# RailroadShield.net
KiCad netlist of a schematic drawn in EAGLE
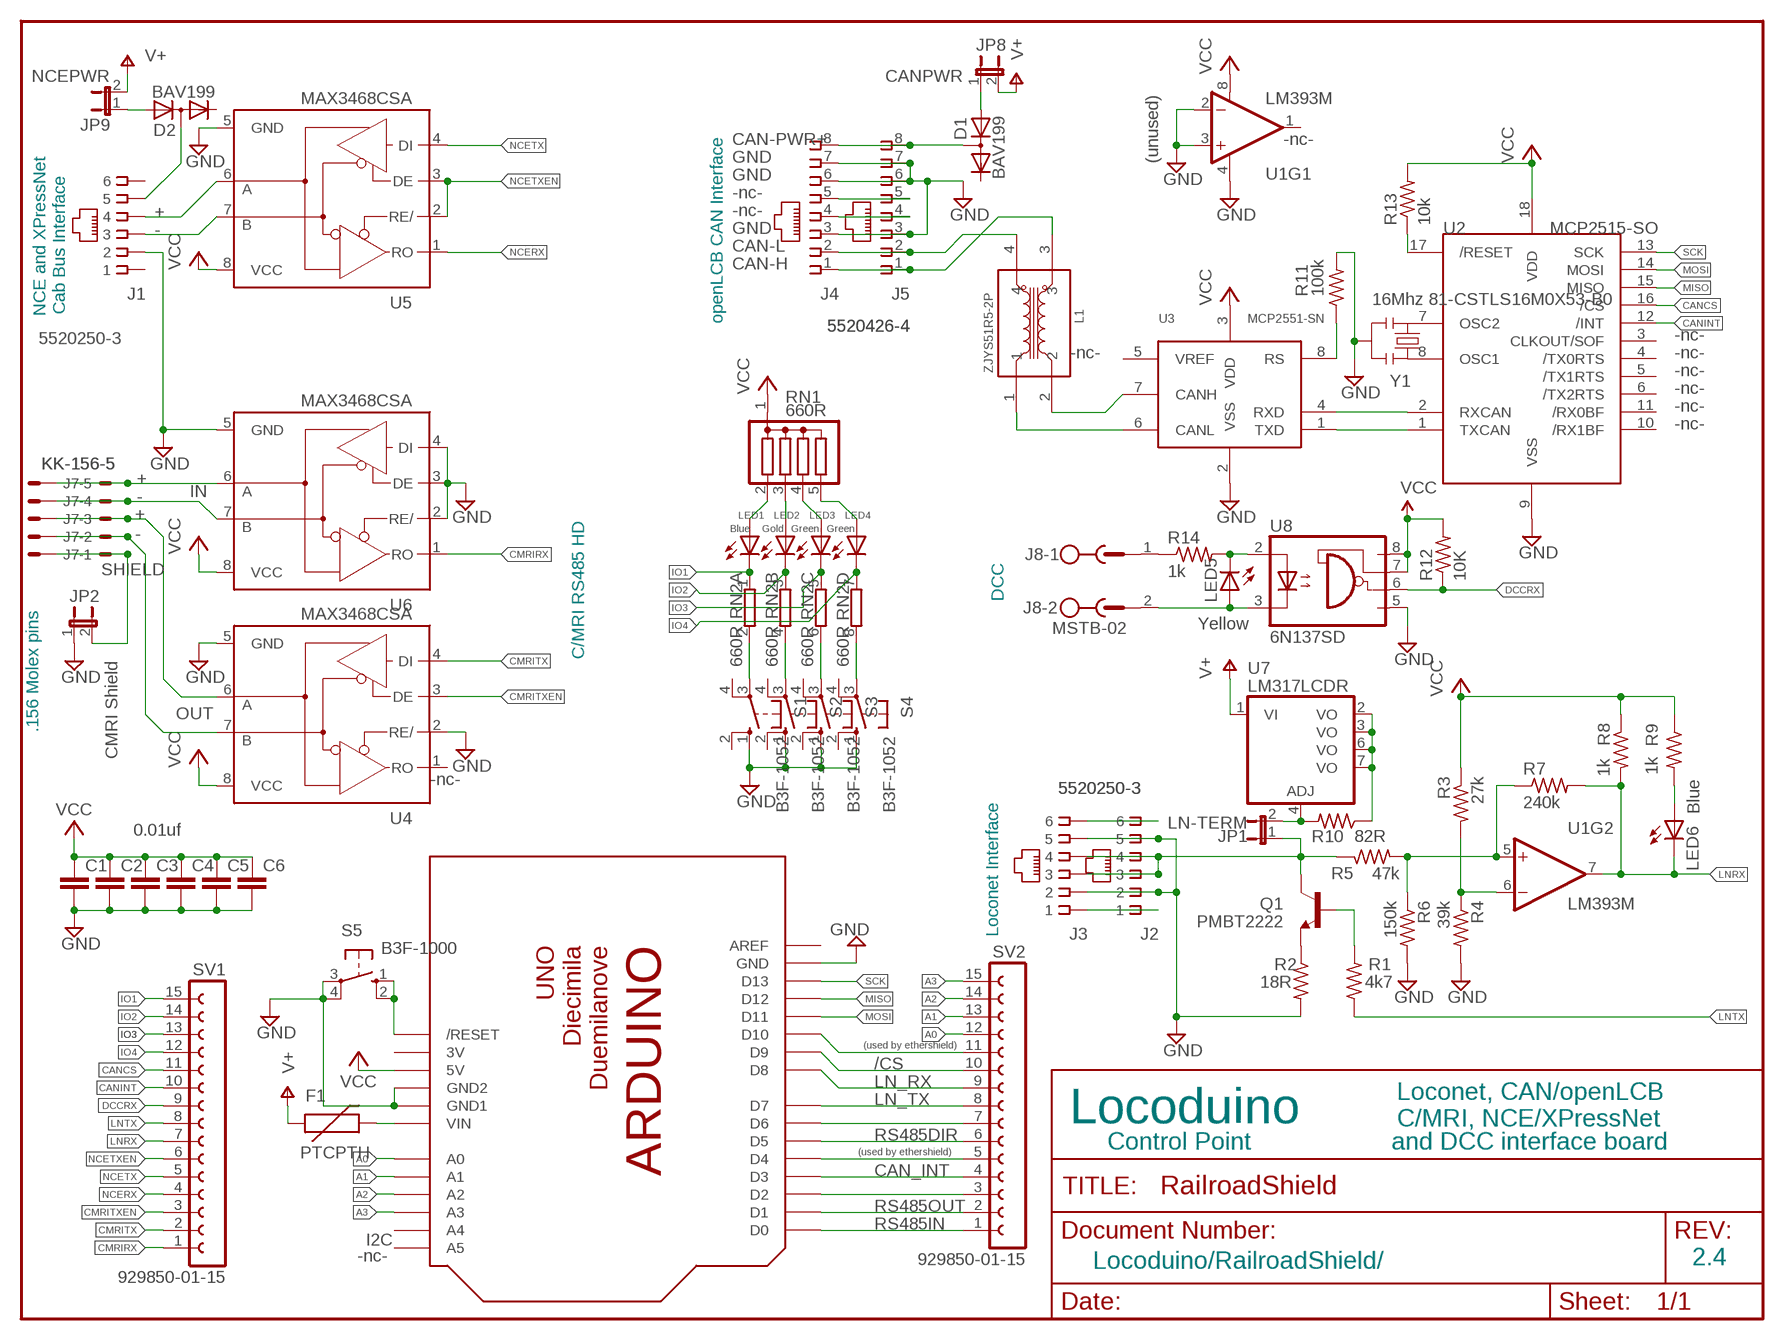
[diagram p0: schematic, sheet 1]

(export (version "E")
  (design (tool "Eeschema 10.0.6"))
  (components
    (comp (ref "C1")
      (value "0.01uf")
      (footprint "eagle-import:0805")
      (libsource (lib "eagle-import") (part "CAP0805"))
    )
    (comp (ref "C2")
      (value "0.01uf")
      (footprint "eagle-import:0805")
      (libsource (lib "eagle-import") (part "CAP0805"))
    )
    (comp (ref "C3")
      (value "0.01uf")
      (footprint "eagle-import:0805")
      (libsource (lib "eagle-import") (part "CAP0805"))
    )
    (comp (ref "C4")
      (value "0.01uf")
      (footprint "eagle-import:0805")
      (libsource (lib "eagle-import") (part "CAP0805"))
    )
    (comp (ref "C5")
      (value "0.01uf")
      (footprint "eagle-import:0805")
      (libsource (lib "eagle-import") (part "CAP0805"))
    )
    (comp (ref "C6")
      (value "0.01uf")
      (footprint "eagle-import:0805")
      (libsource (lib "eagle-import") (part "CAP0805"))
    )
    (comp (ref "D1")
      (value "BAV199")
      (footprint "eagle-import:SOT23")
      (libsource (lib "eagle-import") (part "BAV199"))
    )
    (comp (ref "D2")
      (value "BAV199")
      (footprint "eagle-import:SOT23")
      (libsource (lib "eagle-import") (part "BAV199"))
    )
    (comp (ref "F1")
      (value "PTCPTH")
      (footprint "eagle-import:PTC")
      (libsource (lib "eagle-import") (part "PTCPTH"))
    )
    (comp (ref "J1")
      (value "5520250-3")
      (footprint "eagle-import:RJ11-NO_SHIELD")
      (libsource (lib "eagle-import") (part "RJ11RA-6X"))
    )
    (comp (ref "J2")
      (value "5520250-3")
      (footprint "eagle-import:RJ11-NO_SHIELD")
      (libsource (lib "eagle-import") (part "RJ11RA-6X"))
    )
    (comp (ref "J3")
      (value "5520250-3")
      (footprint "eagle-import:RJ11-NO_SHIELD")
      (libsource (lib "eagle-import") (part "RJ11RA-6X"))
    )
    (comp (ref "J4")
      (value "5520426-4")
      (footprint "eagle-import:RJ45-NO-SHIELD")
      (libsource (lib "eagle-import") (part "RJ45-8X"))
    )
    (comp (ref "J5")
      (value "5520426-4")
      (footprint "eagle-import:RJ45-NO-SHIELD")
      (libsource (lib "eagle-import") (part "RJ45-8X"))
    )
    (comp (ref "J6")
      (value "KK-156-5")
      (footprint "eagle-import:KK-156-5")
      (libsource (lib "eagle-import") (part "KK-156-5"))
    )
    (comp (ref "J7")
      (value "KK-156-5")
      (footprint "eagle-import:KK-156-5")
      (libsource (lib "eagle-import") (part "KK-156-5"))
    )
    (comp (ref "J8")
      (value "MSTB-02")
      (footprint "eagle-import:MSTBV2")
      (libsource (lib "eagle-import") (part "MSTBV2"))
    )
    (comp (ref "JP1")
      (value "LN-TERM")
      (footprint "eagle-import:1X02_LOCK")
      (libsource (lib "eagle-import") (part "JUMPER-2PTH_LOCK"))
    )
    (comp (ref "JP2")
      (value "CMRI Shield")
      (footprint "eagle-import:1X02_LOCK")
      (libsource (lib "eagle-import") (part "JUMPER-2PTH_LOCK"))
    )
    (comp (ref "JP8")
      (value "CANPWR")
      (footprint "eagle-import:1X02_LOCK")
      (libsource (lib "eagle-import") (part "JUMPER-2PTH_LOCK"))
    )
    (comp (ref "JP9")
      (value "NCEPWR")
      (footprint "eagle-import:1X02_LOCK")
      (libsource (lib "eagle-import") (part "JUMPER-2PTH_LOCK"))
    )
    (comp (ref "L1")
      (value "ZJYS51R5-2P")
      (footprint "eagle-import:ZJYS")
      (libsource (lib "eagle-import") (part "ZJYS51R5-2P"))
    )
    (comp (ref "LED1")
      (value "Blue")
      (footprint "eagle-import:CHIP-LED0805")
      (libsource (lib "eagle-import") (part "LEDCHIP-LED0805"))
    )
    (comp (ref "LED2")
      (value "Gold")
      (footprint "eagle-import:CHIP-LED0805")
      (libsource (lib "eagle-import") (part "LEDCHIP-LED0805"))
    )
    (comp (ref "LED3")
      (value "Green")
      (footprint "eagle-import:CHIP-LED0805")
      (libsource (lib "eagle-import") (part "LEDCHIP-LED0805"))
    )
    (comp (ref "LED4")
      (value "Green")
      (footprint "eagle-import:CHIP-LED0805")
      (libsource (lib "eagle-import") (part "LEDCHIP-LED0805"))
    )
    (comp (ref "LED5")
      (value "Yellow")
      (footprint "eagle-import:CHIP-LED0805")
      (libsource (lib "eagle-import") (part "LEDCHIP-LED0805"))
    )
    (comp (ref "LED6")
      (value "Blue")
      (footprint "eagle-import:CHIP-LED0805")
      (libsource (lib "eagle-import") (part "LEDCHIP-LED0805"))
    )
    (comp (ref "Q1")
      (value "PMBT2222")
      (footprint "eagle-import:SOT23-3")
      (libsource (lib "eagle-import") (part "TRANSISTOR_NPNSOT23-3"))
    )
    (comp (ref "R1")
      (value "4k7")
      (footprint "eagle-import:R0805")
      (libsource (lib "eagle-import") (part "R-US_R0805"))
    )
    (comp (ref "R2")
      (value "18R")
      (footprint "eagle-import:R0805")
      (libsource (lib "eagle-import") (part "R-US_R0805"))
    )
    (comp (ref "R3")
      (value "27k")
      (footprint "eagle-import:R0805")
      (libsource (lib "eagle-import") (part "R-US_R0805"))
    )
    (comp (ref "R4")
      (value "39k")
      (footprint "eagle-import:R0805")
      (libsource (lib "eagle-import") (part "R-US_R0805"))
    )
    (comp (ref "R5")
      (value "47k")
      (footprint "eagle-import:R0805")
      (libsource (lib "eagle-import") (part "R-US_R0805"))
    )
    (comp (ref "R6")
      (value "150k")
      (footprint "eagle-import:R0805")
      (libsource (lib "eagle-import") (part "R-US_R0805"))
    )
    (comp (ref "R7")
      (value "240k")
      (footprint "eagle-import:R0805")
      (libsource (lib "eagle-import") (part "R-US_R0805"))
    )
    (comp (ref "R8")
      (value "1k")
      (footprint "eagle-import:R0805")
      (libsource (lib "eagle-import") (part "R-US_R0805"))
    )
    (comp (ref "R9")
      (value "1k")
      (footprint "eagle-import:R0805")
      (libsource (lib "eagle-import") (part "R-US_R0805"))
    )
    (comp (ref "R10")
      (value "82R")
      (footprint "eagle-import:R0805")
      (libsource (lib "eagle-import") (part "R-US_R0805"))
    )
    (comp (ref "R11")
      (value "100k")
      (footprint "eagle-import:R0805")
      (libsource (lib "eagle-import") (part "R-US_R0805"))
    )
    (comp (ref "R12")
      (value "10K")
      (footprint "eagle-import:R0805")
      (libsource (lib "eagle-import") (part "R-US_R0805"))
    )
    (comp (ref "R13")
      (value "10k")
      (footprint "eagle-import:R0805")
      (libsource (lib "eagle-import") (part "R-US_R0805"))
    )
    (comp (ref "R14")
      (value "1k")
      (footprint "eagle-import:R0805")
      (libsource (lib "eagle-import") (part "R-US_R0805"))
    )
    (comp (ref "RN1")
      (value "660R")
      (footprint "eagle-import:SIL5")
      (libsource (lib "eagle-import") (part "G04R"))
    )
    (comp (ref "RN2")
      (value "660R")
      (footprint "eagle-import:SIL8")
      (libsource (lib "eagle-import") (part "E4R"))
    )
    (comp (ref "S1")
      (value "B3F-1052")
      (footprint "eagle-import:B3F-10XX")
      (libsource (lib "eagle-import") (part "10-XX"))
    )
    (comp (ref "S2")
      (value "B3F-1052")
      (footprint "eagle-import:B3F-10XX")
      (libsource (lib "eagle-import") (part "10-XX"))
    )
    (comp (ref "S3")
      (value "B3F-1052")
      (footprint "eagle-import:B3F-10XX")
      (libsource (lib "eagle-import") (part "10-XX"))
    )
    (comp (ref "S4")
      (value "B3F-1052")
      (footprint "eagle-import:B3F-10XX")
      (libsource (lib "eagle-import") (part "10-XX"))
    )
    (comp (ref "S5")
      (value "B3F-1000")
      (footprint "eagle-import:B3F-10XX")
      (libsource (lib "eagle-import") (part "10-XX"))
    )
    (comp (ref "SV1")
      (value "929850-01-15")
      (footprint "eagle-import:FE15")
      (libsource (lib "eagle-import") (part "FE15-1"))
    )
    (comp (ref "SV2")
      (value "929850-01-15")
      (footprint "eagle-import:FE15")
      (libsource (lib "eagle-import") (part "FE15-1"))
    )
    (comp (ref "U$1")
      (value "ARDUINODUEMILANOVE")
      (footprint "eagle-import:ARDUINO-BIGSHIELD")
      (libsource (lib "eagle-import") (part "ARDUINODUEMILANOVE"))
    )
    (comp (ref "U1")
      (value "LM393M")
      (footprint "eagle-import:SO08")
      (libsource (lib "eagle-import") (part "LM393M"))
    )
    (comp (ref "U2")
      (value "MCP2515-SO")
      (footprint "eagle-import:SO-18W")
      (libsource (lib "eagle-import") (part "MCP2515-SO"))
    )
    (comp (ref "U3")
      (value "MCP2551-SN")
      (footprint "eagle-import:SO-08")
      (libsource (lib "eagle-import") (part "MCP2551-SN"))
    )
    (comp (ref "U4")
      (value "MAX3468CSA")
      (footprint "eagle-import:SO08")
      (libsource (lib "eagle-import") (part "MAX34SA68C"))
    )
    (comp (ref "U5")
      (value "MAX3468CSA")
      (footprint "eagle-import:SO08")
      (libsource (lib "eagle-import") (part "MAX34SA68C"))
    )
    (comp (ref "U6")
      (value "MAX3468CSA")
      (footprint "eagle-import:SO08")
      (libsource (lib "eagle-import") (part "MAX34SA68C"))
    )
    (comp (ref "U7")
      (value "LM317LCDR")
      (footprint "eagle-import:SO08")
      (libsource (lib "eagle-import") (part "LM317LD"))
    )
    (comp (ref "U8")
      (value "6N137SD")
      (footprint "eagle-import:SM8")
      (libsource (lib "eagle-import") (part "6N137S"))
    )
    (comp (ref "Y1")
      (value "16Mhz 81-CSTLS16M0X53-B0")
      (footprint "eagle-import:RESONATOR-PTH")
      (libsource (lib "eagle-import") (part "RESONATORPTH"))
    )
  )
  (nets
    (net (code "1") (name "/3V") (class "Default")
      (node (ref "U$1") (pin "3V") (pinfunction "3V_3V") (pintype "power_in"))
    )
    (net (code "2") (name "/CAN-H") (class "Default")
      (node (ref "J4") (pin "1") (pinfunction "1_1") (pintype "passive"))
      (node (ref "J5") (pin "1") (pinfunction "1_1") (pintype "passive"))
      (node (ref "L1") (pin "3") (pinfunction "3_3") (pintype "bidirectional"))
    )
    (net (code "3") (name "/CAN-L") (class "Default")
      (node (ref "J4") (pin "2") (pinfunction "2_2") (pintype "passive"))
      (node (ref "J5") (pin "2") (pinfunction "2_2") (pintype "passive"))
      (node (ref "L1") (pin "4") (pinfunction "4_4") (pintype "bidirectional"))
    )
    (net (code "4") (name "/CAN-PWR+") (class "Default")
      (node (ref "D1") (pin "3") (pinfunction "AC_3") (pintype "passive"))
      (node (ref "J4") (pin "8") (pinfunction "8_8") (pintype "passive"))
      (node (ref "J5") (pin "8") (pinfunction "8_8") (pintype "passive"))
    )
    (net (code "5") (name "A0") (class "Default")
      (node (ref "SV2") (pin "12") (pinfunction "12_12") (pintype "passive"))
      (node (ref "U$1") (pin "A0") (pinfunction "A0_A0") (pintype "bidirectional"))
    )
    (net (code "6") (name "A1") (class "Default")
      (node (ref "SV2") (pin "13") (pinfunction "13_13") (pintype "passive"))
      (node (ref "U$1") (pin "A1") (pinfunction "A1_A1") (pintype "bidirectional"))
    )
    (net (code "7") (name "A2") (class "Default")
      (node (ref "SV2") (pin "14") (pinfunction "14_14") (pintype "passive"))
      (node (ref "U$1") (pin "A2") (pinfunction "A2_A2") (pintype "bidirectional"))
    )
    (net (code "8") (name "A3") (class "Default")
      (node (ref "SV2") (pin "15") (pinfunction "15_15") (pintype "passive"))
      (node (ref "U$1") (pin "A3") (pinfunction "A3_A3") (pintype "bidirectional"))
    )
    (net (code "9") (name "CANCS") (class "Default")
      (node (ref "SV1") (pin "11") (pinfunction "11_11") (pintype "passive"))
      (node (ref "U2") (pin "16") (pinfunction "/CS_16") (pintype "bidirectional"))
    )
    (net (code "10") (name "CANINT") (class "Default")
      (node (ref "SV1") (pin "10") (pinfunction "10_10") (pintype "passive"))
      (node (ref "U2") (pin "12") (pinfunction "/INT_12") (pintype "output"))
    )
    (net (code "11") (name "CMRIRX") (class "Default")
      (node (ref "SV1") (pin "1") (pinfunction "1_1") (pintype "passive"))
      (node (ref "U6") (pin "1") (pinfunction "RO_1") (pintype "output"))
    )
    (net (code "12") (name "CMRITX") (class "Default")
      (node (ref "SV1") (pin "2") (pinfunction "2_2") (pintype "passive"))
      (node (ref "U4") (pin "4") (pinfunction "DI_4") (pintype "input"))
    )
    (net (code "13") (name "CMRITXEN") (class "Default")
      (node (ref "SV1") (pin "3") (pinfunction "3_3") (pintype "passive"))
      (node (ref "U4") (pin "3") (pinfunction "DE_3") (pintype "input"))
    )
    (net (code "14") (name "DCCRX") (class "Default")
      (node (ref "R12") (pin "1") (pinfunction "1_1") (pintype "passive"))
      (node (ref "SV1") (pin "9") (pinfunction "9_9") (pintype "passive"))
      (node (ref "U8") (pin "6") (pinfunction "VO_6") (pintype "passive"))
    )
    (net (code "15") (name "GND") (class "Default")
      (node (ref "C1") (pin "2") (pinfunction "2_2") (pintype "passive"))
      (node (ref "C2") (pin "2") (pinfunction "2_2") (pintype "passive"))
      (node (ref "C3") (pin "2") (pinfunction "2_2") (pintype "passive"))
      (node (ref "C4") (pin "2") (pinfunction "2_2") (pintype "passive"))
      (node (ref "C5") (pin "2") (pinfunction "2_2") (pintype "passive"))
      (node (ref "C6") (pin "2") (pinfunction "2_2") (pintype "passive"))
      (node (ref "J1") (pin "2") (pinfunction "2_2") (pintype "passive"))
      (node (ref "J2") (pin "2") (pinfunction "2_2") (pintype "passive"))
      (node (ref "J2") (pin "5") (pinfunction "5_5") (pintype "passive"))
      (node (ref "J3") (pin "2") (pinfunction "2_2") (pintype "passive"))
      (node (ref "J3") (pin "5") (pinfunction "5_5") (pintype "passive"))
      (node (ref "J4") (pin "3") (pinfunction "3_3") (pintype "passive"))
      (node (ref "J4") (pin "6") (pinfunction "6_6") (pintype "passive"))
      (node (ref "J4") (pin "7") (pinfunction "7_7") (pintype "passive"))
      (node (ref "J5") (pin "3") (pinfunction "3_3") (pintype "passive"))
      (node (ref "J5") (pin "6") (pinfunction "6_6") (pintype "passive"))
      (node (ref "J5") (pin "7") (pinfunction "7_7") (pintype "passive"))
      (node (ref "JP2") (pin "1") (pinfunction "1_1") (pintype "passive"))
      (node (ref "R11") (pin "2") (pinfunction "2_2") (pintype "passive"))
      (node (ref "R2") (pin "2") (pinfunction "2_2") (pintype "passive"))
      (node (ref "R4") (pin "2") (pinfunction "2_2") (pintype "passive"))
      (node (ref "R6") (pin "2") (pinfunction "2_2") (pintype "passive"))
      (node (ref "S1") (pin "1") (pinfunction "S_1") (pintype "passive"))
      (node (ref "S2") (pin "1") (pinfunction "S_1") (pintype "passive"))
      (node (ref "S3") (pin "1") (pinfunction "S_1") (pintype "passive"))
      (node (ref "S4") (pin "1") (pinfunction "S_1") (pintype "passive"))
      (node (ref "S5") (pin "3") (pinfunction "P_3") (pintype "passive"))
      (node (ref "S5") (pin "4") (pinfunction "P1_4") (pintype "passive"))
      (node (ref "U$1") (pin "GND") (pinfunction "GND_GND") (pintype "power_in"))
      (node (ref "U$1") (pin "GND1") (pinfunction "GND1_GND1") (pintype "power_in"))
      (node (ref "U$1") (pin "GND2") (pinfunction "GND2_GND2") (pintype "power_in"))
      (node (ref "U1") (pin "2") (pinfunction "-IN_2") (pintype "input"))
      (node (ref "U1") (pin "3") (pinfunction "+IN_3") (pintype "input"))
      (node (ref "U1") (pin "4") (pinfunction "V-_4") (pintype "power_in"))
      (node (ref "U2") (pin "9") (pinfunction "VSS_9") (pintype "power_in"))
      (node (ref "U3") (pin "2") (pinfunction "VSS_2") (pintype "power_in"))
      (node (ref "U4") (pin "2") (pinfunction "RE/_2") (pintype "input"))
      (node (ref "U4") (pin "5") (pinfunction "GND_5") (pintype "power_in"))
      (node (ref "U5") (pin "5") (pinfunction "GND_5") (pintype "power_in"))
      (node (ref "U6") (pin "2") (pinfunction "RE/_2") (pintype "input"))
      (node (ref "U6") (pin "3") (pinfunction "DE_3") (pintype "input"))
      (node (ref "U6") (pin "4") (pinfunction "DI_4") (pintype "input"))
      (node (ref "U6") (pin "5") (pinfunction "GND_5") (pintype "power_in"))
      (node (ref "U8") (pin "5") (pinfunction "GND_5") (pintype "passive"))
      (node (ref "Y1") (pin "2") (pinfunction "2_2") (pintype "passive"))
    )
    (net (code "16") (name "IO1") (class "Default")
      (node (ref "LED1") (pin "C") (pinfunction "C_C") (pintype "passive"))
      (node (ref "RN2") (pin "1") (pinfunction "1_1") (pintype "passive"))
      (node (ref "SV1") (pin "15") (pinfunction "15_15") (pintype "passive"))
    )
    (net (code "17") (name "IO2") (class "Default")
      (node (ref "LED2") (pin "C") (pinfunction "C_C") (pintype "passive"))
      (node (ref "RN2") (pin "3") (pinfunction "1_3") (pintype "passive"))
      (node (ref "SV1") (pin "14") (pinfunction "14_14") (pintype "passive"))
    )
    (net (code "18") (name "IO3") (class "Default")
      (node (ref "LED3") (pin "C") (pinfunction "C_C") (pintype "passive"))
      (node (ref "RN2") (pin "5") (pinfunction "1_5") (pintype "passive"))
      (node (ref "SV1") (pin "13") (pinfunction "13_13") (pintype "passive"))
    )
    (net (code "19") (name "IO4") (class "Default")
      (node (ref "LED4") (pin "C") (pinfunction "C_C") (pintype "passive"))
      (node (ref "RN2") (pin "7") (pinfunction "1_7") (pintype "passive"))
      (node (ref "SV1") (pin "12") (pinfunction "12_12") (pintype "passive"))
    )
    (net (code "20") (name "LNRX") (class "Default")
      (node (ref "LED6") (pin "C") (pinfunction "C_C") (pintype "passive"))
      (node (ref "R7") (pin "2") (pinfunction "2_2") (pintype "passive"))
      (node (ref "R8") (pin "2") (pinfunction "2_2") (pintype "passive"))
      (node (ref "SV1") (pin "7") (pinfunction "7_7") (pintype "passive"))
      (node (ref "U1") (pin "7") (pinfunction "OUT_7") (pintype "output"))
    )
    (net (code "21") (name "LNTX") (class "Default")
      (node (ref "R1") (pin "1") (pinfunction "1_1") (pintype "passive"))
      (node (ref "SV1") (pin "8") (pinfunction "8_8") (pintype "passive"))
    )
    (net (code "22") (name "MISO") (class "Default")
      (node (ref "U$1") (pin "D12") (pinfunction "D12_D12") (pintype "bidirectional"))
      (node (ref "U2") (pin "15") (pinfunction "MISO_15") (pintype "bidirectional"))
    )
    (net (code "23") (name "MOSI") (class "Default")
      (node (ref "U$1") (pin "D11") (pinfunction "D11_D11") (pintype "bidirectional"))
      (node (ref "U2") (pin "14") (pinfunction "MOSI_14") (pintype "bidirectional"))
    )
    (net (code "24") (name "NCERX") (class "Default")
      (node (ref "SV1") (pin "4") (pinfunction "4_4") (pintype "passive"))
      (node (ref "U5") (pin "1") (pinfunction "RO_1") (pintype "output"))
    )
    (net (code "25") (name "NCETX") (class "Default")
      (node (ref "SV1") (pin "5") (pinfunction "5_5") (pintype "passive"))
      (node (ref "U5") (pin "4") (pinfunction "DI_4") (pintype "input"))
    )
    (net (code "26") (name "NCETXEN") (class "Default")
      (node (ref "SV1") (pin "6") (pinfunction "6_6") (pintype "passive"))
      (node (ref "U5") (pin "2") (pinfunction "RE/_2") (pintype "input"))
      (node (ref "U5") (pin "3") (pinfunction "DE_3") (pintype "input"))
    )
    (net (code "27") (name "Net-(D1-A)") (class "Default")
      (node (ref "D1") (pin "1") (pinfunction "A_1") (pintype "passive"))
      (node (ref "JP8") (pin "1") (pinfunction "1_1") (pintype "passive"))
    )
    (net (code "28") (name "Net-(D2-A)") (class "Default")
      (node (ref "D2") (pin "1") (pinfunction "A_1") (pintype "passive"))
      (node (ref "JP9") (pin "1") (pinfunction "1_1") (pintype "passive"))
    )
    (net (code "29") (name "Net-(D2-AC)") (class "Default")
      (node (ref "D2") (pin "3") (pinfunction "AC_3") (pintype "passive"))
      (node (ref "J1") (pin "5") (pinfunction "5_5") (pintype "passive"))
    )
    (net (code "30") (name "Net-(F1-2)") (class "Default")
      (node (ref "F1") (pin "P$2") (pinfunction "2_P$2") (pintype "bidirectional"))
      (node (ref "U$1") (pin "VIN") (pinfunction "VIN_VIN") (pintype "power_in"))
    )
    (net (code "31") (name "Net-(J2-Pad1)") (class "Default")
      (node (ref "J2") (pin "1") (pinfunction "1_1") (pintype "passive"))
      (node (ref "J3") (pin "1") (pinfunction "1_1") (pintype "passive"))
    )
    (net (code "32") (name "Net-(J2-Pad6)") (class "Default")
      (node (ref "J2") (pin "6") (pinfunction "6_6") (pintype "passive"))
      (node (ref "J3") (pin "6") (pinfunction "6_6") (pintype "passive"))
    )
    (net (code "33") (name "Net-(J4-Pad4)") (class "Default")
      (node (ref "J4") (pin "4") (pinfunction "4_4") (pintype "passive"))
      (node (ref "J5") (pin "4") (pinfunction "4_4") (pintype "passive"))
    )
    (net (code "34") (name "Net-(J4-Pad5)") (class "Default")
      (node (ref "J4") (pin "5") (pinfunction "5_5") (pintype "passive"))
      (node (ref "J5") (pin "5") (pinfunction "5_5") (pintype "passive"))
    )
    (net (code "35") (name "Net-(J6A-S)") (class "Default")
      (node (ref "J6") (pin "1") (pinfunction "S_1") (pintype "passive"))
      (node (ref "J7") (pin "1") (pinfunction "S_1") (pintype "passive"))
      (node (ref "JP2") (pin "2") (pinfunction "2_2") (pintype "passive"))
    )
    (net (code "36") (name "Net-(J6B-S)") (class "Default")
      (node (ref "J6") (pin "2") (pinfunction "S_2") (pintype "passive"))
      (node (ref "J7") (pin "2") (pinfunction "S_2") (pintype "passive"))
      (node (ref "U4") (pin "7") (pinfunction "B_7") (pintype "passive"))
    )
    (net (code "37") (name "Net-(J6C-S)") (class "Default")
      (node (ref "J6") (pin "3") (pinfunction "S_3") (pintype "passive"))
      (node (ref "J7") (pin "3") (pinfunction "S_3") (pintype "passive"))
      (node (ref "U4") (pin "6") (pinfunction "A_6") (pintype "passive"))
    )
    (net (code "38") (name "Net-(J6D-S)") (class "Default")
      (node (ref "J6") (pin "4") (pinfunction "S_4") (pintype "passive"))
      (node (ref "J7") (pin "4") (pinfunction "S_4") (pintype "passive"))
      (node (ref "U6") (pin "7") (pinfunction "B_7") (pintype "passive"))
    )
    (net (code "39") (name "Net-(J6E-S)") (class "Default")
      (node (ref "J6") (pin "5") (pinfunction "S_5") (pintype "passive"))
      (node (ref "J7") (pin "5") (pinfunction "S_5") (pintype "passive"))
      (node (ref "U6") (pin "6") (pinfunction "A_6") (pintype "passive"))
    )
    (net (code "40") (name "Net-(J8A-SK)") (class "Default")
      (node (ref "J8") (pin "1") (pinfunction "SK_1") (pintype "passive"))
      (node (ref "R14") (pin "1") (pinfunction "1_1") (pintype "passive"))
    )
    (net (code "41") (name "Net-(J8B-SK)") (class "Default")
      (node (ref "J8") (pin "2") (pinfunction "SK_2") (pintype "passive"))
      (node (ref "LED5") (pin "A") (pinfunction "A_A") (pintype "passive"))
      (node (ref "U8") (pin "3") (pinfunction "C_3") (pintype "passive"))
    )
    (net (code "42") (name "Net-(LED1-PadA)") (class "Default")
      (node (ref "LED1") (pin "A") (pinfunction "A_A") (pintype "passive"))
      (node (ref "RN1") (pin "2") (pinfunction "2_2") (pintype "passive"))
    )
    (net (code "43") (name "Net-(LED2-PadA)") (class "Default")
      (node (ref "LED2") (pin "A") (pinfunction "A_A") (pintype "passive"))
      (node (ref "RN1") (pin "3") (pinfunction "3_3") (pintype "passive"))
    )
    (net (code "44") (name "Net-(LED3-PadA)") (class "Default")
      (node (ref "LED3") (pin "A") (pinfunction "A_A") (pintype "passive"))
      (node (ref "RN1") (pin "4") (pinfunction "4_4") (pintype "passive"))
    )
    (net (code "45") (name "Net-(LED4-PadA)") (class "Default")
      (node (ref "LED4") (pin "A") (pinfunction "A_A") (pintype "passive"))
      (node (ref "RN1") (pin "5") (pinfunction "5_5") (pintype "passive"))
    )
    (net (code "46") (name "Net-(LED6-PadA)") (class "Default")
      (node (ref "LED6") (pin "A") (pinfunction "A_A") (pintype "passive"))
      (node (ref "R9") (pin "2") (pinfunction "2_2") (pintype "passive"))
    )
    (net (code "47") (name "Net-(Q1-B)") (class "Default")
      (node (ref "Q1") (pin "1") (pinfunction "B_1") (pintype "passive"))
      (node (ref "R1") (pin "2") (pinfunction "2_2") (pintype "passive"))
    )
    (net (code "48") (name "Net-(Q1-C)") (class "Default")
      (node (ref "J2") (pin "3") (pinfunction "3_3") (pintype "passive"))
      (node (ref "J2") (pin "4") (pinfunction "4_4") (pintype "passive"))
      (node (ref "J3") (pin "3") (pinfunction "3_3") (pintype "passive"))
      (node (ref "J3") (pin "4") (pinfunction "4_4") (pintype "passive"))
      (node (ref "JP1") (pin "1") (pinfunction "1_1") (pintype "passive"))
      (node (ref "Q1") (pin "3") (pinfunction "C_3") (pintype "passive"))
      (node (ref "R5") (pin "1") (pinfunction "1_1") (pintype "passive"))
    )
    (net (code "49") (name "Net-(Q1-E)") (class "Default")
      (node (ref "Q1") (pin "2") (pinfunction "E_2") (pintype "passive"))
      (node (ref "R2") (pin "1") (pinfunction "1_1") (pintype "passive"))
    )
    (net (code "50") (name "Net-(R10-Pad1)") (class "Default")
      (node (ref "R10") (pin "1") (pinfunction "1_1") (pintype "passive"))
      (node (ref "U7") (pin "2") (pinfunction "VO_2") (pintype "passive"))
      (node (ref "U7") (pin "3") (pinfunction "VO_3") (pintype "passive"))
      (node (ref "U7") (pin "6") (pinfunction "VO_6") (pintype "passive"))
      (node (ref "U7") (pin "7") (pinfunction "VO_7") (pintype "passive"))
    )
    (net (code "51") (name "Net-(RN2B-2)") (class "Default")
      (node (ref "RN2") (pin "4") (pinfunction "2_4") (pintype "passive"))
      (node (ref "S2") (pin "3") (pinfunction "P_3") (pintype "passive"))
    )
    (net (code "52") (name "Net-(RN2C-2)") (class "Default")
      (node (ref "RN2") (pin "6") (pinfunction "2_6") (pintype "passive"))
      (node (ref "S3") (pin "3") (pinfunction "P_3") (pintype "passive"))
    )
    (net (code "53") (name "Net-(RN2D-2)") (class "Default")
      (node (ref "RN2") (pin "8") (pinfunction "2_8") (pintype "passive"))
      (node (ref "S4") (pin "3") (pinfunction "P_3") (pintype "passive"))
    )
    (net (code "54") (name "Net-(S1-P)") (class "Default")
      (node (ref "RN2") (pin "2") (pinfunction "2_2") (pintype "passive"))
      (node (ref "S1") (pin "3") (pinfunction "P_3") (pintype "passive"))
    )
    (net (code "55") (name "Net-(S5-S)") (class "Default")
      (node (ref "S5") (pin "1") (pinfunction "S_1") (pintype "passive"))
      (node (ref "S5") (pin "2") (pinfunction "S1_2") (pintype "passive"))
      (node (ref "U$1") (pin "RESET") (pinfunction "/RESET_RESET") (pintype "bidirectional"))
    )
    (net (code "56") (name "Net-(SV2-Pad1)") (class "Default")
      (node (ref "SV2") (pin "1") (pinfunction "1_1") (pintype "passive"))
      (node (ref "U$1") (pin "D0") (pinfunction "D0_D0") (pintype "bidirectional"))
    )
    (net (code "57") (name "Net-(SV2-Pad2)") (class "Default")
      (node (ref "SV2") (pin "2") (pinfunction "2_2") (pintype "passive"))
      (node (ref "U$1") (pin "D1") (pinfunction "D1_D1") (pintype "bidirectional"))
    )
    (net (code "58") (name "Net-(SV2-Pad3)") (class "Default")
      (node (ref "SV2") (pin "3") (pinfunction "3_3") (pintype "passive"))
      (node (ref "U$1") (pin "D2") (pinfunction "D2_D2") (pintype "bidirectional"))
    )
    (net (code "59") (name "Net-(SV2-Pad4)") (class "Default")
      (node (ref "SV2") (pin "4") (pinfunction "4_4") (pintype "passive"))
      (node (ref "U$1") (pin "D3") (pinfunction "D3_D3") (pintype "bidirectional"))
    )
    (net (code "60") (name "Net-(SV2-Pad5)") (class "Default")
      (node (ref "SV2") (pin "5") (pinfunction "5_5") (pintype "passive"))
      (node (ref "U$1") (pin "D4") (pinfunction "D4_D4") (pintype "bidirectional"))
    )
    (net (code "61") (name "Net-(SV2-Pad6)") (class "Default")
      (node (ref "SV2") (pin "6") (pinfunction "6_6") (pintype "passive"))
      (node (ref "U$1") (pin "D5") (pinfunction "D5_D5") (pintype "bidirectional"))
    )
    (net (code "62") (name "Net-(SV2-Pad7)") (class "Default")
      (node (ref "SV2") (pin "7") (pinfunction "7_7") (pintype "passive"))
      (node (ref "U$1") (pin "D6") (pinfunction "D6_D6") (pintype "bidirectional"))
    )
    (net (code "63") (name "Net-(SV2-Pad8)") (class "Default")
      (node (ref "SV2") (pin "8") (pinfunction "8_8") (pintype "passive"))
      (node (ref "U$1") (pin "D7") (pinfunction "D7_D7") (pintype "bidirectional"))
    )
    (net (code "64") (name "Net-(SV2-Pad9)") (class "Default")
      (node (ref "SV2") (pin "9") (pinfunction "9_9") (pintype "passive"))
      (node (ref "U$1") (pin "D8") (pinfunction "D8_D8") (pintype "bidirectional"))
    )
    (net (code "65") (name "Net-(SV2-Pad10)") (class "Default")
      (node (ref "SV2") (pin "10") (pinfunction "10_10") (pintype "passive"))
      (node (ref "U$1") (pin "D9") (pinfunction "D9_D9") (pintype "bidirectional"))
    )
    (net (code "66") (name "Net-(SV2-Pad11)") (class "Default")
      (node (ref "SV2") (pin "11") (pinfunction "11_11") (pintype "passive"))
      (node (ref "U$1") (pin "D10") (pinfunction "D10_D10") (pintype "bidirectional"))
    )
    (net (code "67") (name "Net-(U1B-+IN)") (class "Default")
      (node (ref "R5") (pin "2") (pinfunction "2_2") (pintype "passive"))
      (node (ref "R6") (pin "1") (pinfunction "1_1") (pintype "passive"))
      (node (ref "R7") (pin "1") (pinfunction "1_1") (pintype "passive"))
      (node (ref "U1") (pin "5") (pinfunction "+IN_5") (pintype "input"))
    )
    (net (code "68") (name "Net-(U1B--IN)") (class "Default")
      (node (ref "R3") (pin "2") (pinfunction "2_2") (pintype "passive"))
      (node (ref "R4") (pin "1") (pinfunction "1_1") (pintype "passive"))
      (node (ref "U1") (pin "6") (pinfunction "-IN_6") (pintype "input"))
    )
    (net (code "69") (name "Net-(U2-OSC1)") (class "Default")
      (node (ref "U2") (pin "8") (pinfunction "OSC1_8") (pintype "input"))
      (node (ref "Y1") (pin "3") (pinfunction "3_3") (pintype "passive"))
    )
    (net (code "70") (name "Net-(U2-OSC2)") (class "Default")
      (node (ref "U2") (pin "7") (pinfunction "OSC2_7") (pintype "input"))
      (node (ref "Y1") (pin "1") (pinfunction "1_1") (pintype "passive"))
    )
    (net (code "71") (name "Net-(U2-RXCAN)") (class "Default")
      (node (ref "U2") (pin "2") (pinfunction "RXCAN_2") (pintype "input"))
      (node (ref "U3") (pin "4") (pinfunction "RXD_4") (pintype "bidirectional"))
    )
    (net (code "72") (name "Net-(U2-TXCAN)") (class "Default")
      (node (ref "U2") (pin "1") (pinfunction "TXCAN_1") (pintype "output"))
      (node (ref "U3") (pin "1") (pinfunction "TXD_1") (pintype "bidirectional"))
    )
    (net (code "73") (name "Net-(U2-{slash}RESET)") (class "Default")
      (node (ref "R13") (pin "1") (pinfunction "1_1") (pintype "passive"))
      (node (ref "U2") (pin "17") (pinfunction "/RESET_17") (pintype "bidirectional"))
    )
    (net (code "74") (name "Net-(U3-CANH)") (class "Default")
      (node (ref "L1") (pin "2") (pinfunction "2_2") (pintype "bidirectional"))
      (node (ref "U3") (pin "7") (pinfunction "CANH_7") (pintype "bidirectional"))
    )
    (net (code "75") (name "Net-(U3-CANL)") (class "Default")
      (node (ref "L1") (pin "1") (pinfunction "1_1") (pintype "bidirectional"))
      (node (ref "U3") (pin "6") (pinfunction "CANL_6") (pintype "bidirectional"))
    )
    (net (code "76") (name "Net-(U3-RS)") (class "Default")
      (node (ref "R11") (pin "1") (pinfunction "1_1") (pintype "passive"))
      (node (ref "U3") (pin "8") (pinfunction "RS_8") (pintype "bidirectional"))
    )
    (net (code "77") (name "Net-(U5-A)") (class "Default")
      (node (ref "J1") (pin "4") (pinfunction "4_4") (pintype "passive"))
      (node (ref "U5") (pin "6") (pinfunction "A_6") (pintype "passive"))
    )
    (net (code "78") (name "Net-(U5-B)") (class "Default")
      (node (ref "J1") (pin "3") (pinfunction "3_3") (pintype "passive"))
      (node (ref "U5") (pin "7") (pinfunction "B_7") (pintype "passive"))
    )
    (net (code "79") (name "Net-(U7-ADJ)") (class "Default")
      (node (ref "JP1") (pin "2") (pinfunction "2_2") (pintype "passive"))
      (node (ref "R10") (pin "2") (pinfunction "2_2") (pintype "passive"))
      (node (ref "U7") (pin "4") (pinfunction "ADJ_4") (pintype "input"))
    )
    (net (code "80") (name "Net-(U8-A)") (class "Default")
      (node (ref "LED5") (pin "C") (pinfunction "C_C") (pintype "passive"))
      (node (ref "R14") (pin "2") (pinfunction "2_2") (pintype "passive"))
      (node (ref "U8") (pin "2") (pinfunction "A_2") (pintype "passive"))
    )
    (net (code "81") (name "SCK") (class "Default")
      (node (ref "U$1") (pin "D13") (pinfunction "D13_D13") (pintype "bidirectional"))
      (node (ref "U2") (pin "13") (pinfunction "SCK_13") (pintype "bidirectional"))
    )
    (net (code "82") (name "V+") (class "Default")
      (node (ref "F1") (pin "P$1") (pinfunction "1_P$1") (pintype "bidirectional"))
      (node (ref "JP8") (pin "2") (pinfunction "2_2") (pintype "passive"))
      (node (ref "JP9") (pin "2") (pinfunction "2_2") (pintype "passive"))
      (node (ref "U7") (pin "1") (pinfunction "VI_1") (pintype "input"))
    )
    (net (code "83") (name "VCC") (class "Default")
      (node (ref "C1") (pin "1") (pinfunction "1_1") (pintype "passive"))
      (node (ref "C2") (pin "1") (pinfunction "1_1") (pintype "passive"))
      (node (ref "C3") (pin "1") (pinfunction "1_1") (pintype "passive"))
      (node (ref "C4") (pin "1") (pinfunction "1_1") (pintype "passive"))
      (node (ref "C5") (pin "1") (pinfunction "1_1") (pintype "passive"))
      (node (ref "C6") (pin "1") (pinfunction "1_1") (pintype "passive"))
      (node (ref "R12") (pin "2") (pinfunction "2_2") (pintype "passive"))
      (node (ref "R13") (pin "2") (pinfunction "2_2") (pintype "passive"))
      (node (ref "R3") (pin "1") (pinfunction "1_1") (pintype "passive"))
      (node (ref "R8") (pin "1") (pinfunction "1_1") (pintype "passive"))
      (node (ref "R9") (pin "1") (pinfunction "1_1") (pintype "passive"))
      (node (ref "RN1") (pin "1") (pinfunction "1_1") (pintype "passive"))
      (node (ref "U$1") (pin "5V") (pinfunction "5V_5V") (pintype "power_in"))
      (node (ref "U1") (pin "8") (pinfunction "V+_8") (pintype "power_in"))
      (node (ref "U2") (pin "18") (pinfunction "VDD_18") (pintype "power_in"))
      (node (ref "U3") (pin "3") (pinfunction "VDD_3") (pintype "power_in"))
      (node (ref "U4") (pin "8") (pinfunction "VCC_8") (pintype "power_in"))
      (node (ref "U5") (pin "8") (pinfunction "VCC_8") (pintype "power_in"))
      (node (ref "U6") (pin "8") (pinfunction "VCC_8") (pintype "power_in"))
      (node (ref "U8") (pin "7") (pinfunction "VE_7") (pintype "passive"))
      (node (ref "U8") (pin "8") (pinfunction "VCC_8") (pintype "passive"))
    )
    (net (code "84") (name "unconnected-(D1-C-Pad2)") (class "Default")
      (node (ref "D1") (pin "2") (pinfunction "C_2") (pintype "passive"))
    )
    (net (code "85") (name "unconnected-(D2-C-Pad2)") (class "Default")
      (node (ref "D2") (pin "2") (pinfunction "C_2") (pintype "passive"))
    )
    (net (code "86") (name "unconnected-(J1-Pad1)") (class "Default")
      (node (ref "J1") (pin "1") (pinfunction "1_1") (pintype "passive"))
    )
    (net (code "87") (name "unconnected-(J1-Pad6)") (class "Default")
      (node (ref "J1") (pin "6") (pinfunction "6_6") (pintype "passive"))
    )
    (net (code "88") (name "unconnected-(S1-P1-Pad4)") (class "Default")
      (node (ref "S1") (pin "4") (pinfunction "P1_4") (pintype "passive"))
    )
    (net (code "89") (name "unconnected-(S1-S1-Pad2)") (class "Default")
      (node (ref "S1") (pin "2") (pinfunction "S1_2") (pintype "passive"))
    )
    (net (code "90") (name "unconnected-(S2-P1-Pad4)") (class "Default")
      (node (ref "S2") (pin "4") (pinfunction "P1_4") (pintype "passive"))
    )
    (net (code "91") (name "unconnected-(S2-S1-Pad2)") (class "Default")
      (node (ref "S2") (pin "2") (pinfunction "S1_2") (pintype "passive"))
    )
    (net (code "92") (name "unconnected-(S3-P1-Pad4)") (class "Default")
      (node (ref "S3") (pin "4") (pinfunction "P1_4") (pintype "passive"))
    )
    (net (code "93") (name "unconnected-(S3-S1-Pad2)") (class "Default")
      (node (ref "S3") (pin "2") (pinfunction "S1_2") (pintype "passive"))
    )
    (net (code "94") (name "unconnected-(S4-P1-Pad4)") (class "Default")
      (node (ref "S4") (pin "4") (pinfunction "P1_4") (pintype "passive"))
    )
    (net (code "95") (name "unconnected-(S4-S1-Pad2)") (class "Default")
      (node (ref "S4") (pin "2") (pinfunction "S1_2") (pintype "passive"))
    )
    (net (code "96") (name "unconnected-(U$1-PadA4)") (class "Default")
      (node (ref "U$1") (pin "A4") (pinfunction "A4_A4") (pintype "bidirectional"))
    )
    (net (code "97") (name "unconnected-(U$1-PadA5)") (class "Default")
      (node (ref "U$1") (pin "A5") (pinfunction "A5_A5") (pintype "bidirectional"))
    )
    (net (code "98") (name "unconnected-(U$1-PadAREF)") (class "Default")
      (node (ref "U$1") (pin "AREF") (pinfunction "AREF_AREF") (pintype "bidirectional"))
    )
    (net (code "99") (name "unconnected-(U1A-OUT-Pad1)") (class "Default")
      (node (ref "U1") (pin "1") (pinfunction "OUT_1") (pintype "output"))
    )
    (net (code "100") (name "unconnected-(U2-CLKOUT{slash}SOF-Pad3)") (class "Default")
      (node (ref "U2") (pin "3") (pinfunction "CLKOUT/SOF_3") (pintype "bidirectional"))
    )
    (net (code "101") (name "unconnected-(U2-{slash}RX0BF-Pad11)") (class "Default")
      (node (ref "U2") (pin "11") (pinfunction "/RX0BF_11") (pintype "bidirectional"))
    )
    (net (code "102") (name "unconnected-(U2-{slash}RX1BF-Pad10)") (class "Default")
      (node (ref "U2") (pin "10") (pinfunction "/RX1BF_10") (pintype "bidirectional"))
    )
    (net (code "103") (name "unconnected-(U2-{slash}TX0RTS-Pad4)") (class "Default")
      (node (ref "U2") (pin "4") (pinfunction "/TX0RTS_4") (pintype "bidirectional"))
    )
    (net (code "104") (name "unconnected-(U2-{slash}TX1RTS-Pad5)") (class "Default")
      (node (ref "U2") (pin "5") (pinfunction "/TX1RTS_5") (pintype "bidirectional"))
    )
    (net (code "105") (name "unconnected-(U2-{slash}TX2RTS-Pad6)") (class "Default")
      (node (ref "U2") (pin "6") (pinfunction "/TX2RTS_6") (pintype "bidirectional"))
    )
    (net (code "106") (name "unconnected-(U3-VREF-Pad5)") (class "Default")
      (node (ref "U3") (pin "5") (pinfunction "VREF_5") (pintype "bidirectional"))
    )
    (net (code "107") (name "unconnected-(U4-RO-Pad1)") (class "Default")
      (node (ref "U4") (pin "1") (pinfunction "RO_1") (pintype "output"))
    )
  )
)
